# RS485.net
KiCad netlist of a schematic drawn in Altium Designer
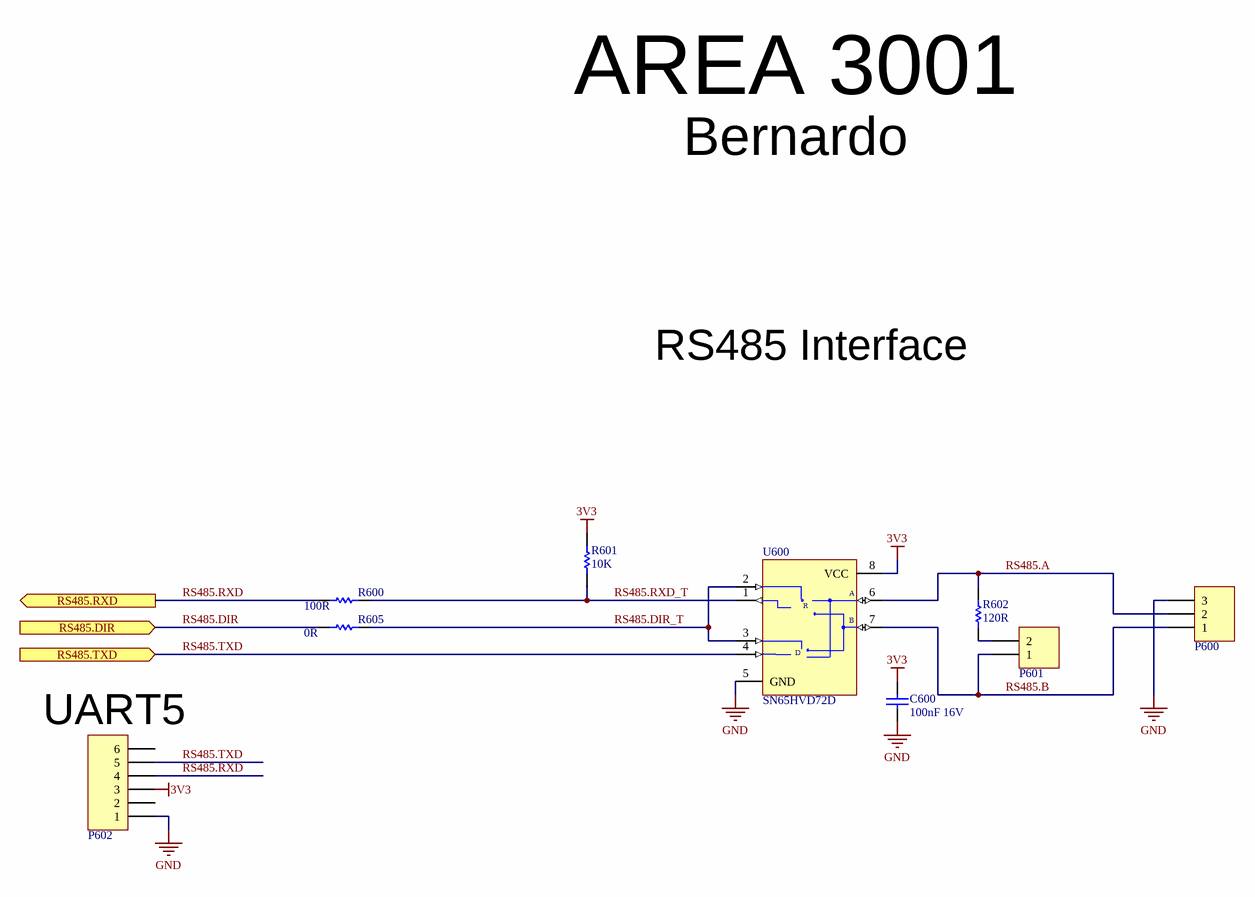
[diagram p0: RS485.SchDoc]

(export (version "E")
  (design (tool "Eeschema 10.0.6"))
  (components
    (comp (ref "C600")
      (value "100nF 16V")
      (footprint "C0603_N")
      (description "Capacitor Ceramic")
      (fields (field (name "Comment") "CAP_CERAMIC"))
      (libsource (lib "Phyx_Components") (part "CAP_CERAMIC"))
    )
    (comp (ref "P600")
      (value "3 Terminal Socket 2,5mm")
      (footprint "WE_691382000003")
      (libsource (lib "Phyx_Components") (part "Header 3"))
    )
    (comp (ref "P601")
      (value "Header 2")
      (footprint "HDR1X2")
      (libsource (lib "Phyx_Components") (part "Header 2"))
    )
    (comp (ref "P602")
      (value "Header 6")
      (footprint "HDR1X6")
      (libsource (lib "Phyx_Components") (part "Header 6"))
    )
    (comp (ref "R600")
      (value "100R")
      (footprint "R0603_N")
      (fields (field (name "Comment") "RESISTOR"))
      (libsource (lib "Phyx_Components") (part "RESISTOR"))
    )
    (comp (ref "R601")
      (value "10K")
      (footprint "R0603_N")
      (fields (field (name "Comment") "RESISTOR"))
      (libsource (lib "Phyx_Components") (part "RESISTOR"))
    )
    (comp (ref "R602")
      (value "120R")
      (footprint "R1206")
      (fields (field (name "Comment") "RESISTOR"))
      (libsource (lib "Phyx_Components") (part "RESISTOR"))
    )
    (comp (ref "R605")
      (value "0R")
      (footprint "R0603_N")
      (fields (field (name "Comment") "RESISTOR"))
      (libsource (lib "Phyx_Components") (part "RESISTOR"))
    )
    (comp (ref "U600")
      (value "SN65HVD72D")
      (footprint "SOIC_N_8")
      (fields (field (name "Comment") "RS-485 3V3 Transceiver 250kbps"))
      (libsource (lib "Phyx_Components") (part "MAX485"))
    )
  )
  (nets
    (net (code "1") (name "/RS485.A") (class "Default")
      (node (ref "P600") (pin "2") (pinfunction "2_2") (pintype "passive"))
      (node (ref "R602") (pin "1") (pinfunction "1_1") (pintype "passive"))
      (node (ref "U600") (pin "6") (pinfunction "A_6") (pintype "bidirectional"))
    )
    (net (code "2") (name "/RS485.B") (class "Default")
      (node (ref "P600") (pin "1") (pinfunction "1_1") (pintype "passive"))
      (node (ref "P601") (pin "1") (pinfunction "1_1") (pintype "passive"))
      (node (ref "U600") (pin "7") (pinfunction "B_7") (pintype "bidirectional"))
    )
    (net (code "3") (name "/RS485.DIR") (class "Default")
      (node (ref "R605") (pin "2") (pinfunction "2_2") (pintype "passive"))
    )
    (net (code "4") (name "/RS485.DIR_T") (class "Default")
      (node (ref "R605") (pin "1") (pinfunction "1_1") (pintype "passive"))
      (node (ref "U600") (pin "2") (pinfunction "~{RE}_2") (pintype "input"))
      (node (ref "U600") (pin "3") (pinfunction "DE_3") (pintype "input"))
    )
    (net (code "5") (name "/RS485.RXD") (class "Default")
      (node (ref "P602") (pin "4") (pinfunction "4_4") (pintype "passive"))
      (node (ref "R600") (pin "2") (pinfunction "2_2") (pintype "passive"))
    )
    (net (code "6") (name "/RS485.RXD_T") (class "Default")
      (node (ref "R600") (pin "1") (pinfunction "1_1") (pintype "passive"))
      (node (ref "R601") (pin "2") (pinfunction "2_2") (pintype "passive"))
      (node (ref "U600") (pin "1") (pinfunction "RO_1") (pintype "output"))
    )
    (net (code "7") (name "/RS485.TXD") (class "Default")
      (node (ref "P602") (pin "5") (pinfunction "5_5") (pintype "passive"))
      (node (ref "U600") (pin "4") (pinfunction "DI_4") (pintype "input"))
    )
    (net (code "8") (name "3V3") (class "Default")
      (node (ref "C600") (pin "1") (pinfunction "1_1") (pintype "passive"))
      (node (ref "P602") (pin "3") (pinfunction "3_3") (pintype "passive"))
      (node (ref "R601") (pin "1") (pinfunction "1_1") (pintype "passive"))
      (node (ref "U600") (pin "8") (pinfunction "VCC_8") (pintype "power_in"))
    )
    (net (code "9") (name "GND") (class "Default")
      (node (ref "C600") (pin "2") (pinfunction "2_2") (pintype "passive"))
      (node (ref "P600") (pin "3") (pinfunction "3_3") (pintype "passive"))
      (node (ref "P602") (pin "1") (pinfunction "1_1") (pintype "passive"))
      (node (ref "U600") (pin "5") (pinfunction "GND_5") (pintype "power_in"))
    )
    (net (code "10") (name "Net-(P601-Pad2)") (class "Default")
      (node (ref "P601") (pin "2") (pinfunction "2_2") (pintype "passive"))
      (node (ref "R602") (pin "2") (pinfunction "2_2") (pintype "passive"))
    )
    (net (code "11") (name "unconnected-(P602-Pad2)") (class "Default")
      (node (ref "P602") (pin "2") (pinfunction "2_2") (pintype "passive"))
    )
    (net (code "12") (name "unconnected-(P602-Pad6)") (class "Default")
      (node (ref "P602") (pin "6") (pinfunction "6_6") (pintype "passive"))
    )
  )
)
